# esp32.net
KiCad netlist of a schematic drawn in EAGLE
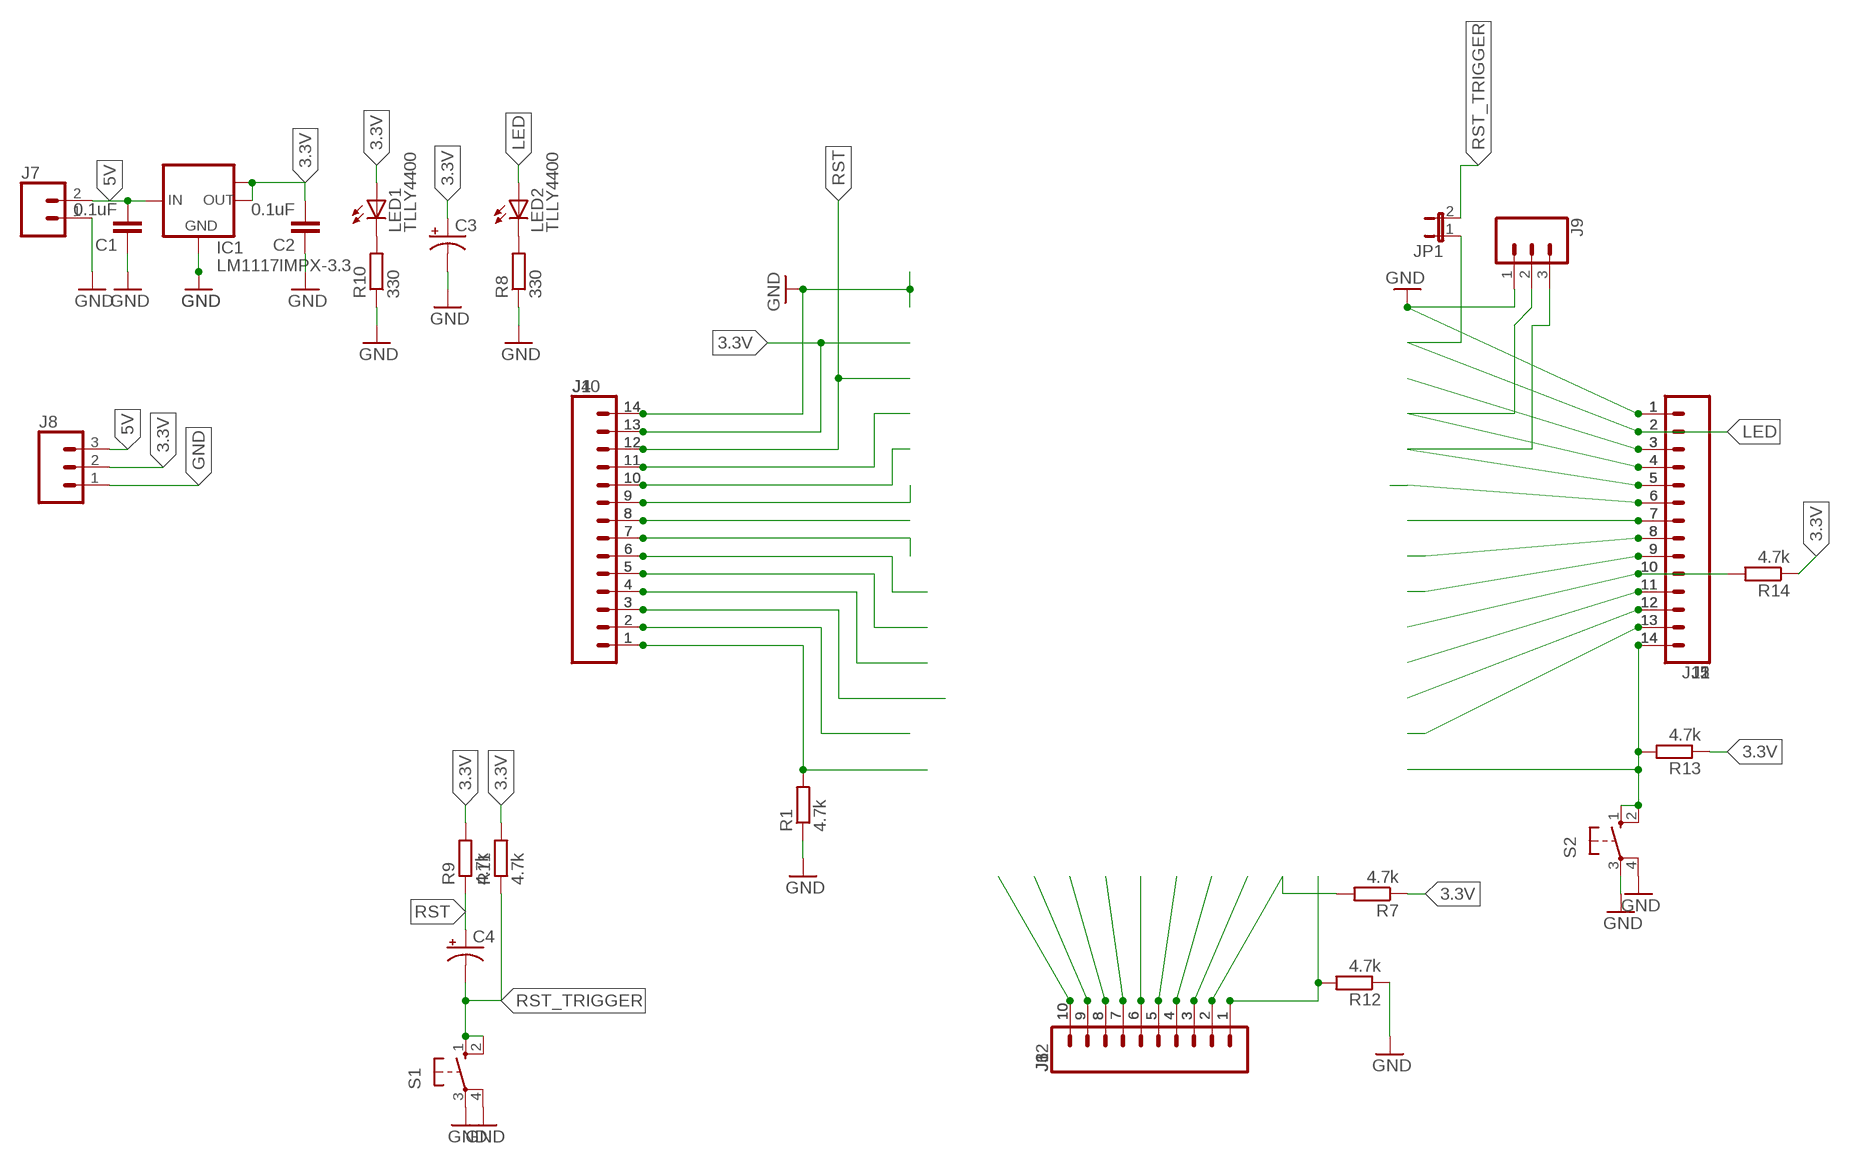
[diagram p0: schematic, sheet 1]

(export (version "E")
  (design (tool "Eeschema 10.0.6"))
  (components
    (comp (ref "C1")
      (value "0.1uF")
      (footprint "eagle-import:CAP-PTH-SMALL-KIT")
      (libsource (lib "eagle-import") (part "0.1UF-KIT-EZ-50V-20%"))
    )
    (comp (ref "C2")
      (value "0.1uF")
      (footprint "eagle-import:CAP-PTH-SMALL-KIT")
      (libsource (lib "eagle-import") (part "0.1UF-KIT-EZ-50V-20%"))
    )
    (comp (ref "C3")
      (value "CPOL-USE3.5-8")
      (footprint "eagle-import:E3,5-8")
      (libsource (lib "eagle-import") (part "CPOL-USE3.5-8"))
    )
    (comp (ref "C4")
      (value "CPOL-USE3.5-8")
      (footprint "eagle-import:E3,5-8")
      (libsource (lib "eagle-import") (part "CPOL-USE3.5-8"))
    )
    (comp (ref "IC1")
      (value "LM1117IMPX-3.3")
      (footprint "eagle-import:SOT223")
      (libsource (lib "eagle-import") (part "LM1117IMPX-3.3"))
    )
    (comp (ref "J1")
      (value "CONN_14LONGPADS")
      (footprint "eagle-import:1X14-LONGPADS")
      (libsource (lib "eagle-import") (part "CONN_14LONGPADS"))
    )
    (comp (ref "J2")
      (value "CONN_14LONGPADS")
      (footprint "eagle-import:1X14-LONGPADS")
      (libsource (lib "eagle-import") (part "CONN_14LONGPADS"))
    )
    (comp (ref "J3")
      (value "CONN_10\"")
      (footprint "eagle-import:1X10")
      (libsource (lib "eagle-import") (part "CONN_10{dblquote}"))
    )
    (comp (ref "J4")
      (value "CONN_14LONGPADS")
      (footprint "eagle-import:1X14-LONGPADS")
      (libsource (lib "eagle-import") (part "CONN_14LONGPADS"))
    )
    (comp (ref "J5")
      (value "CONN_14LONGPADS")
      (footprint "eagle-import:1X14-LONGPADS")
      (libsource (lib "eagle-import") (part "CONN_14LONGPADS"))
    )
    (comp (ref "J6")
      (value "CONN_10\"")
      (footprint "eagle-import:1X10")
      (libsource (lib "eagle-import") (part "CONN_10{dblquote}"))
    )
    (comp (ref "J7")
      (value "CONN_023.5MM")
      (footprint "eagle-import:SCREWTERMINAL-3.5MM-2")
      (libsource (lib "eagle-import") (part "CONN_023.5MM"))
    )
    (comp (ref "J8")
      (value "CONN_03")
      (footprint "eagle-import:1X03")
      (libsource (lib "eagle-import") (part "CONN_03"))
    )
    (comp (ref "J9")
      (value "CONN_03")
      (footprint "eagle-import:1X03")
      (libsource (lib "eagle-import") (part "CONN_03"))
    )
    (comp (ref "J10")
      (value "CONN_14LONGPADS")
      (footprint "eagle-import:1X14-LONGPADS")
      (libsource (lib "eagle-import") (part "CONN_14LONGPADS"))
    )
    (comp (ref "J11")
      (value "CONN_14LONGPADS")
      (footprint "eagle-import:1X14-LONGPADS")
      (libsource (lib "eagle-import") (part "CONN_14LONGPADS"))
    )
    (comp (ref "J12")
      (value "CONN_10\"")
      (footprint "eagle-import:1X10")
      (libsource (lib "eagle-import") (part "CONN_10{dblquote}"))
    )
    (comp (ref "JP1")
      (value "JP1E")
      (footprint "eagle-import:JP1")
      (libsource (lib "eagle-import") (part "JP1E"))
    )
    (comp (ref "LED1")
      (value "TLLY4400")
      (footprint "eagle-import:LED3MM")
      (fields (field (name "MF") "VISHAY SEMICONDUCTOR"))
      (libsource (lib "eagle-import") (part "TLLY4400"))
    )
    (comp (ref "LED2")
      (value "TLLY4400")
      (footprint "eagle-import:LED3MM")
      (fields (field (name "MF") "VISHAY SEMICONDUCTOR"))
      (libsource (lib "eagle-import") (part "TLLY4400"))
    )
    (comp (ref "R1")
      (value "4.7k")
      (footprint "eagle-import:0207_12")
      (libsource (lib "eagle-import") (part "R-EU_0207/12"))
    )
    (comp (ref "R7")
      (value "4.7k")
      (footprint "eagle-import:0207_12")
      (libsource (lib "eagle-import") (part "R-EU_0207/12"))
    )
    (comp (ref "R8")
      (value "330")
      (footprint "eagle-import:0207_12")
      (libsource (lib "eagle-import") (part "R-EU_0207/12"))
    )
    (comp (ref "R9")
      (value "4.7k")
      (footprint "eagle-import:0207_12")
      (libsource (lib "eagle-import") (part "R-EU_0207/12"))
    )
    (comp (ref "R10")
      (value "330")
      (footprint "eagle-import:0207_12")
      (libsource (lib "eagle-import") (part "R-EU_0207/12"))
    )
    (comp (ref "R11")
      (value "4.7k")
      (footprint "eagle-import:0207_12")
      (libsource (lib "eagle-import") (part "R-EU_0207/12"))
    )
    (comp (ref "R12")
      (value "4.7k")
      (footprint "eagle-import:0207_12")
      (libsource (lib "eagle-import") (part "R-EU_0207/12"))
    )
    (comp (ref "R13")
      (value "4.7k")
      (footprint "eagle-import:0207_12")
      (libsource (lib "eagle-import") (part "R-EU_0207/12"))
    )
    (comp (ref "R14")
      (value "4.7k")
      (footprint "eagle-import:0207_12")
      (libsource (lib "eagle-import") (part "R-EU_0207/12"))
    )
    (comp (ref "S1")
      (value "10-XX")
      (footprint "eagle-import:B3F-10XX")
      (fields (field (name "MPN") "B3F-1000"))
      (libsource (lib "eagle-import") (part "10-XX"))
    )
    (comp (ref "S2")
      (value "10-XX")
      (footprint "eagle-import:B3F-10XX")
      (fields (field (name "MPN") "B3F-1000"))
      (libsource (lib "eagle-import") (part "10-XX"))
    )
  )
  (nets
    (net (code "1") (name "3.3V") (class "Default")
      (node (ref "C2") (pin "2") (pinfunction "2_2") (pintype "passive"))
      (node (ref "C3") (pin "+") (pinfunction "+_+") (pintype "passive"))
      (node (ref "IC1") (pin "2") (pinfunction "OUT_2") (pintype "passive"))
      (node (ref "IC1") (pin "TAB") (pinfunction "OUT1_TAB") (pintype "passive"))
      (node (ref "J1") (pin "13") (pinfunction "13_13") (pintype "passive"))
      (node (ref "J10") (pin "13") (pinfunction "13_13") (pintype "passive"))
      (node (ref "J4") (pin "13") (pinfunction "13_13") (pintype "passive"))
      (node (ref "J8") (pin "2") (pinfunction "2_2") (pintype "passive"))
      (node (ref "LED1") (pin "A") (pinfunction "A_A") (pintype "passive"))
      (node (ref "R11") (pin "2") (pinfunction "2_2") (pintype "passive"))
      (node (ref "R13") (pin "1") (pinfunction "1_1") (pintype "passive"))
      (node (ref "R14") (pin "1") (pinfunction "1_1") (pintype "passive"))
      (node (ref "R7") (pin "1") (pinfunction "1_1") (pintype "passive"))
      (node (ref "R9") (pin "2") (pinfunction "2_2") (pintype "passive"))
    )
    (net (code "2") (name "5V") (class "Default")
      (node (ref "C1") (pin "2") (pinfunction "2_2") (pintype "passive"))
      (node (ref "IC1") (pin "3") (pinfunction "IN_3") (pintype "input"))
      (node (ref "J7") (pin "2") (pinfunction "2_2") (pintype "passive"))
      (node (ref "J8") (pin "3") (pinfunction "3_3") (pintype "passive"))
    )
    (net (code "3") (name "GND") (class "Default")
      (node (ref "C1") (pin "1") (pinfunction "1_1") (pintype "passive"))
      (node (ref "C2") (pin "1") (pinfunction "1_1") (pintype "passive"))
      (node (ref "C3") (pin "-") (pinfunction "-_-") (pintype "passive"))
      (node (ref "IC1") (pin "1") (pinfunction "GND_1") (pintype "input"))
      (node (ref "J1") (pin "14") (pinfunction "14_14") (pintype "passive"))
      (node (ref "J10") (pin "14") (pinfunction "14_14") (pintype "passive"))
      (node (ref "J11") (pin "1") (pinfunction "1_1") (pintype "passive"))
      (node (ref "J12") (pin "10") (pinfunction "10_10") (pintype "passive"))
      (node (ref "J2") (pin "1") (pinfunction "1_1") (pintype "passive"))
      (node (ref "J3") (pin "10") (pinfunction "10_10") (pintype "passive"))
      (node (ref "J4") (pin "14") (pinfunction "14_14") (pintype "passive"))
      (node (ref "J5") (pin "1") (pinfunction "1_1") (pintype "passive"))
      (node (ref "J6") (pin "10") (pinfunction "10_10") (pintype "passive"))
      (node (ref "J7") (pin "1") (pinfunction "1_1") (pintype "passive"))
      (node (ref "J8") (pin "1") (pinfunction "1_1") (pintype "passive"))
      (node (ref "J9") (pin "1") (pinfunction "1_1") (pintype "passive"))
      (node (ref "R1") (pin "1") (pinfunction "1_1") (pintype "passive"))
      (node (ref "R10") (pin "1") (pinfunction "1_1") (pintype "passive"))
      (node (ref "R12") (pin "1") (pinfunction "1_1") (pintype "passive"))
      (node (ref "R8") (pin "1") (pinfunction "1_1") (pintype "passive"))
      (node (ref "S1") (pin "3") (pinfunction "P_3") (pintype "passive"))
      (node (ref "S1") (pin "4") (pinfunction "P1_4") (pintype "passive"))
      (node (ref "S2") (pin "3") (pinfunction "P_3") (pintype "passive"))
      (node (ref "S2") (pin "4") (pinfunction "P1_4") (pintype "passive"))
    )
    (net (code "4") (name "LED") (class "Default")
      (node (ref "J11") (pin "2") (pinfunction "2_2") (pintype "passive"))
      (node (ref "J2") (pin "2") (pinfunction "2_2") (pintype "passive"))
      (node (ref "J5") (pin "2") (pinfunction "2_2") (pintype "passive"))
      (node (ref "JP1") (pin "1") (pinfunction "1_1") (pintype "passive"))
      (node (ref "LED2") (pin "A") (pinfunction "A_A") (pintype "passive"))
    )
    (net (code "5") (name "Net-(J1-Pad1)") (class "Default")
      (node (ref "J1") (pin "1") (pinfunction "1_1") (pintype "passive"))
      (node (ref "J10") (pin "1") (pinfunction "1_1") (pintype "passive"))
      (node (ref "J4") (pin "1") (pinfunction "1_1") (pintype "passive"))
      (node (ref "R1") (pin "2") (pinfunction "2_2") (pintype "passive"))
    )
    (net (code "6") (name "Net-(J1-Pad2)") (class "Default")
      (node (ref "J1") (pin "2") (pinfunction "2_2") (pintype "passive"))
      (node (ref "J10") (pin "2") (pinfunction "2_2") (pintype "passive"))
      (node (ref "J4") (pin "2") (pinfunction "2_2") (pintype "passive"))
    )
    (net (code "7") (name "Net-(J1-Pad3)") (class "Default")
      (node (ref "J1") (pin "3") (pinfunction "3_3") (pintype "passive"))
      (node (ref "J10") (pin "3") (pinfunction "3_3") (pintype "passive"))
      (node (ref "J4") (pin "3") (pinfunction "3_3") (pintype "passive"))
    )
    (net (code "8") (name "Net-(J1-Pad4)") (class "Default")
      (node (ref "J1") (pin "4") (pinfunction "4_4") (pintype "passive"))
      (node (ref "J10") (pin "4") (pinfunction "4_4") (pintype "passive"))
      (node (ref "J4") (pin "4") (pinfunction "4_4") (pintype "passive"))
    )
    (net (code "9") (name "Net-(J1-Pad5)") (class "Default")
      (node (ref "J1") (pin "5") (pinfunction "5_5") (pintype "passive"))
      (node (ref "J10") (pin "5") (pinfunction "5_5") (pintype "passive"))
      (node (ref "J4") (pin "5") (pinfunction "5_5") (pintype "passive"))
    )
    (net (code "10") (name "Net-(J1-Pad6)") (class "Default")
      (node (ref "J1") (pin "6") (pinfunction "6_6") (pintype "passive"))
      (node (ref "J10") (pin "6") (pinfunction "6_6") (pintype "passive"))
      (node (ref "J4") (pin "6") (pinfunction "6_6") (pintype "passive"))
    )
    (net (code "11") (name "Net-(J1-Pad7)") (class "Default")
      (node (ref "J1") (pin "7") (pinfunction "7_7") (pintype "passive"))
      (node (ref "J10") (pin "7") (pinfunction "7_7") (pintype "passive"))
      (node (ref "J4") (pin "7") (pinfunction "7_7") (pintype "passive"))
    )
    (net (code "12") (name "Net-(J1-Pad8)") (class "Default")
      (node (ref "J1") (pin "8") (pinfunction "8_8") (pintype "passive"))
      (node (ref "J10") (pin "8") (pinfunction "8_8") (pintype "passive"))
      (node (ref "J4") (pin "8") (pinfunction "8_8") (pintype "passive"))
    )
    (net (code "13") (name "Net-(J1-Pad9)") (class "Default")
      (node (ref "J1") (pin "9") (pinfunction "9_9") (pintype "passive"))
      (node (ref "J10") (pin "9") (pinfunction "9_9") (pintype "passive"))
      (node (ref "J4") (pin "9") (pinfunction "9_9") (pintype "passive"))
    )
    (net (code "14") (name "Net-(J1-Pad10)") (class "Default")
      (node (ref "J1") (pin "10") (pinfunction "10_10") (pintype "passive"))
      (node (ref "J10") (pin "10") (pinfunction "10_10") (pintype "passive"))
      (node (ref "J4") (pin "10") (pinfunction "10_10") (pintype "passive"))
    )
    (net (code "15") (name "Net-(J1-Pad11)") (class "Default")
      (node (ref "J1") (pin "11") (pinfunction "11_11") (pintype "passive"))
      (node (ref "J10") (pin "11") (pinfunction "11_11") (pintype "passive"))
      (node (ref "J4") (pin "11") (pinfunction "11_11") (pintype "passive"))
    )
    (net (code "16") (name "Net-(J11-Pad3)") (class "Default")
      (node (ref "J11") (pin "3") (pinfunction "3_3") (pintype "passive"))
      (node (ref "J2") (pin "3") (pinfunction "3_3") (pintype "passive"))
      (node (ref "J5") (pin "3") (pinfunction "3_3") (pintype "passive"))
    )
    (net (code "17") (name "Net-(J11-Pad4)") (class "Default")
      (node (ref "J11") (pin "4") (pinfunction "4_4") (pintype "passive"))
      (node (ref "J2") (pin "4") (pinfunction "4_4") (pintype "passive"))
      (node (ref "J5") (pin "4") (pinfunction "4_4") (pintype "passive"))
      (node (ref "J9") (pin "2") (pinfunction "2_2") (pintype "passive"))
    )
    (net (code "18") (name "Net-(J11-Pad5)") (class "Default")
      (node (ref "J11") (pin "5") (pinfunction "5_5") (pintype "passive"))
      (node (ref "J2") (pin "5") (pinfunction "5_5") (pintype "passive"))
      (node (ref "J5") (pin "5") (pinfunction "5_5") (pintype "passive"))
      (node (ref "J9") (pin "3") (pinfunction "3_3") (pintype "passive"))
    )
    (net (code "19") (name "Net-(J11-Pad6)") (class "Default")
      (node (ref "J11") (pin "6") (pinfunction "6_6") (pintype "passive"))
      (node (ref "J2") (pin "6") (pinfunction "6_6") (pintype "passive"))
      (node (ref "J5") (pin "6") (pinfunction "6_6") (pintype "passive"))
    )
    (net (code "20") (name "Net-(J11-Pad7)") (class "Default")
      (node (ref "J11") (pin "7") (pinfunction "7_7") (pintype "passive"))
      (node (ref "J2") (pin "7") (pinfunction "7_7") (pintype "passive"))
      (node (ref "J5") (pin "7") (pinfunction "7_7") (pintype "passive"))
    )
    (net (code "21") (name "Net-(J11-Pad8)") (class "Default")
      (node (ref "J11") (pin "8") (pinfunction "8_8") (pintype "passive"))
      (node (ref "J2") (pin "8") (pinfunction "8_8") (pintype "passive"))
      (node (ref "J5") (pin "8") (pinfunction "8_8") (pintype "passive"))
    )
    (net (code "22") (name "Net-(J11-Pad9)") (class "Default")
      (node (ref "J11") (pin "9") (pinfunction "9_9") (pintype "passive"))
      (node (ref "J2") (pin "9") (pinfunction "9_9") (pintype "passive"))
      (node (ref "J5") (pin "9") (pinfunction "9_9") (pintype "passive"))
    )
    (net (code "23") (name "Net-(J11-Pad10)") (class "Default")
      (node (ref "J11") (pin "10") (pinfunction "10_10") (pintype "passive"))
      (node (ref "J2") (pin "10") (pinfunction "10_10") (pintype "passive"))
      (node (ref "J5") (pin "10") (pinfunction "10_10") (pintype "passive"))
      (node (ref "R14") (pin "2") (pinfunction "2_2") (pintype "passive"))
    )
    (net (code "24") (name "Net-(J11-Pad11)") (class "Default")
      (node (ref "J11") (pin "11") (pinfunction "11_11") (pintype "passive"))
      (node (ref "J2") (pin "11") (pinfunction "11_11") (pintype "passive"))
      (node (ref "J5") (pin "11") (pinfunction "11_11") (pintype "passive"))
    )
    (net (code "25") (name "Net-(J11-Pad12)") (class "Default")
      (node (ref "J11") (pin "12") (pinfunction "12_12") (pintype "passive"))
      (node (ref "J2") (pin "12") (pinfunction "12_12") (pintype "passive"))
      (node (ref "J5") (pin "12") (pinfunction "12_12") (pintype "passive"))
    )
    (net (code "26") (name "Net-(J11-Pad13)") (class "Default")
      (node (ref "J11") (pin "13") (pinfunction "13_13") (pintype "passive"))
      (node (ref "J2") (pin "13") (pinfunction "13_13") (pintype "passive"))
      (node (ref "J5") (pin "13") (pinfunction "13_13") (pintype "passive"))
    )
    (net (code "27") (name "Net-(J12-Pad1)") (class "Default")
      (node (ref "J12") (pin "1") (pinfunction "1_1") (pintype "passive"))
      (node (ref "J3") (pin "1") (pinfunction "1_1") (pintype "passive"))
      (node (ref "J6") (pin "1") (pinfunction "1_1") (pintype "passive"))
      (node (ref "R12") (pin "2") (pinfunction "2_2") (pintype "passive"))
    )
    (net (code "28") (name "Net-(J12-Pad2)") (class "Default")
      (node (ref "J12") (pin "2") (pinfunction "2_2") (pintype "passive"))
      (node (ref "J3") (pin "2") (pinfunction "2_2") (pintype "passive"))
      (node (ref "J6") (pin "2") (pinfunction "2_2") (pintype "passive"))
      (node (ref "R7") (pin "2") (pinfunction "2_2") (pintype "passive"))
    )
    (net (code "29") (name "Net-(J12-Pad3)") (class "Default")
      (node (ref "J12") (pin "3") (pinfunction "3_3") (pintype "passive"))
      (node (ref "J3") (pin "3") (pinfunction "3_3") (pintype "passive"))
      (node (ref "J6") (pin "3") (pinfunction "3_3") (pintype "passive"))
    )
    (net (code "30") (name "Net-(J12-Pad4)") (class "Default")
      (node (ref "J12") (pin "4") (pinfunction "4_4") (pintype "passive"))
      (node (ref "J3") (pin "4") (pinfunction "4_4") (pintype "passive"))
      (node (ref "J6") (pin "4") (pinfunction "4_4") (pintype "passive"))
    )
    (net (code "31") (name "Net-(J12-Pad5)") (class "Default")
      (node (ref "J12") (pin "5") (pinfunction "5_5") (pintype "passive"))
      (node (ref "J3") (pin "5") (pinfunction "5_5") (pintype "passive"))
      (node (ref "J6") (pin "5") (pinfunction "5_5") (pintype "passive"))
    )
    (net (code "32") (name "Net-(J12-Pad6)") (class "Default")
      (node (ref "J12") (pin "6") (pinfunction "6_6") (pintype "passive"))
      (node (ref "J3") (pin "6") (pinfunction "6_6") (pintype "passive"))
      (node (ref "J6") (pin "6") (pinfunction "6_6") (pintype "passive"))
    )
    (net (code "33") (name "Net-(J12-Pad7)") (class "Default")
      (node (ref "J12") (pin "7") (pinfunction "7_7") (pintype "passive"))
      (node (ref "J3") (pin "7") (pinfunction "7_7") (pintype "passive"))
      (node (ref "J6") (pin "7") (pinfunction "7_7") (pintype "passive"))
    )
    (net (code "34") (name "Net-(J12-Pad8)") (class "Default")
      (node (ref "J12") (pin "8") (pinfunction "8_8") (pintype "passive"))
      (node (ref "J3") (pin "8") (pinfunction "8_8") (pintype "passive"))
      (node (ref "J6") (pin "8") (pinfunction "8_8") (pintype "passive"))
    )
    (net (code "35") (name "Net-(J12-Pad9)") (class "Default")
      (node (ref "J12") (pin "9") (pinfunction "9_9") (pintype "passive"))
      (node (ref "J3") (pin "9") (pinfunction "9_9") (pintype "passive"))
      (node (ref "J6") (pin "9") (pinfunction "9_9") (pintype "passive"))
    )
    (net (code "36") (name "Net-(LED1-C)") (class "Default")
      (node (ref "LED1") (pin "K") (pinfunction "C_K") (pintype "passive"))
      (node (ref "R10") (pin "2") (pinfunction "2_2") (pintype "passive"))
    )
    (net (code "37") (name "Net-(LED2-C)") (class "Default")
      (node (ref "LED2") (pin "K") (pinfunction "C_K") (pintype "passive"))
      (node (ref "R8") (pin "2") (pinfunction "2_2") (pintype "passive"))
    )
    (net (code "38") (name "Net-(S2-S)") (class "Default")
      (node (ref "J11") (pin "14") (pinfunction "14_14") (pintype "passive"))
      (node (ref "J2") (pin "14") (pinfunction "14_14") (pintype "passive"))
      (node (ref "J5") (pin "14") (pinfunction "14_14") (pintype "passive"))
      (node (ref "R13") (pin "2") (pinfunction "2_2") (pintype "passive"))
      (node (ref "S2") (pin "1") (pinfunction "S_1") (pintype "passive"))
      (node (ref "S2") (pin "2") (pinfunction "S1_2") (pintype "passive"))
    )
    (net (code "39") (name "RST") (class "Default")
      (node (ref "C4") (pin "+") (pinfunction "+_+") (pintype "passive"))
      (node (ref "J1") (pin "12") (pinfunction "12_12") (pintype "passive"))
      (node (ref "J10") (pin "12") (pinfunction "12_12") (pintype "passive"))
      (node (ref "J4") (pin "12") (pinfunction "12_12") (pintype "passive"))
      (node (ref "R9") (pin "1") (pinfunction "1_1") (pintype "passive"))
    )
    (net (code "40") (name "RST_TRIGGER") (class "Default")
      (node (ref "C4") (pin "-") (pinfunction "-_-") (pintype "passive"))
      (node (ref "JP1") (pin "2") (pinfunction "2_2") (pintype "passive"))
      (node (ref "R11") (pin "1") (pinfunction "1_1") (pintype "passive"))
      (node (ref "S1") (pin "1") (pinfunction "S_1") (pintype "passive"))
      (node (ref "S1") (pin "2") (pinfunction "S1_2") (pintype "passive"))
    )
  )
)
